# OLD_Main.net
KiCad netlist of a schematic drawn in Altium Designer
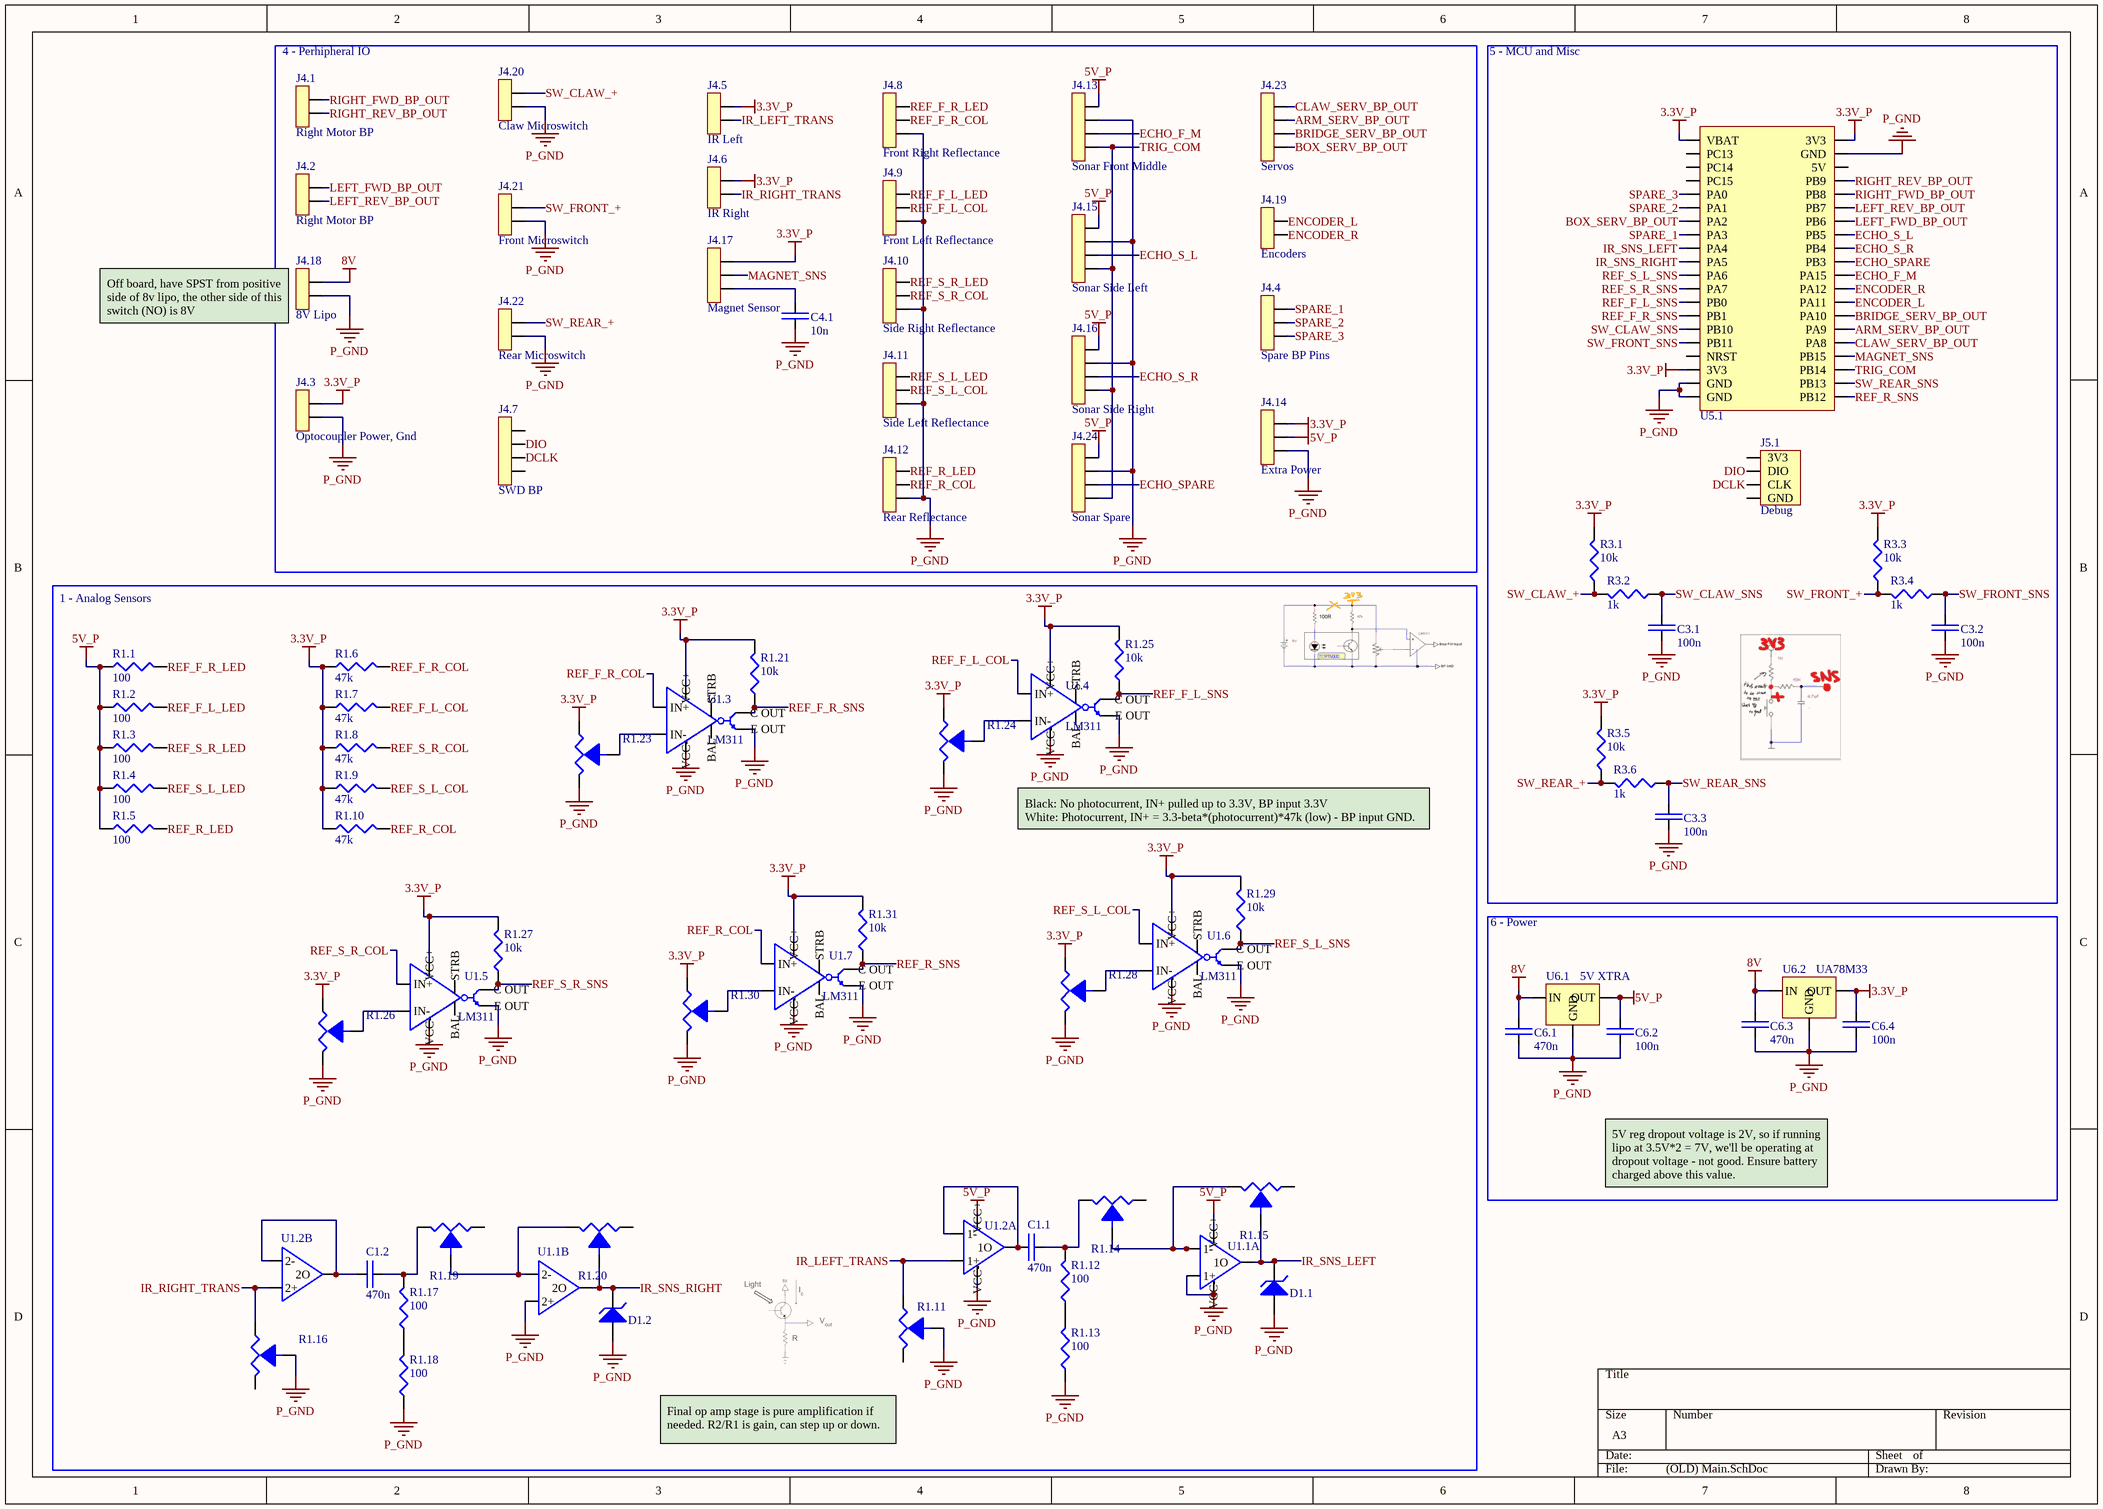
[diagram p0: (OLD) Main.SchDoc]

(export (version "E")
  (design (tool "Eeschema 10.0.6"))
  (components
    (comp (ref "C1.1")
      (value "470n")
      (footprint "Non Polarized Cap")
      (libsource (lib "SPICEBot_SchLib") (part "Cap_Generic"))
    )
    (comp (ref "C1.2")
      (value "470n")
      (footprint "Non Polarized Cap")
      (libsource (lib "SPICEBot_SchLib") (part "Cap_Generic"))
    )
    (comp (ref "C3.1")
      (value "100n")
      (footprint "Non Polarized Cap")
      (libsource (lib "SPICEBot_SchLib") (part "Cap_Generic"))
    )
    (comp (ref "C3.2")
      (value "100n")
      (footprint "Non Polarized Cap")
      (libsource (lib "SPICEBot_SchLib") (part "Cap_Generic"))
    )
    (comp (ref "C3.3")
      (value "100n")
      (footprint "Non Polarized Cap")
      (libsource (lib "SPICEBot_SchLib") (part "Cap_Generic"))
    )
    (comp (ref "C4.1")
      (value "10n")
      (footprint "Non Polarized Cap")
      (libsource (lib "SPICEBot_SchLib") (part "Cap_Generic"))
    )
    (comp (ref "C6.1")
      (value "470n")
      (footprint "Non Polarized Cap")
      (libsource (lib "SPICEBot_SchLib") (part "Cap_Generic"))
    )
    (comp (ref "C6.2")
      (value "100n")
      (footprint "Non Polarized Cap")
      (libsource (lib "SPICEBot_SchLib") (part "Cap_Generic"))
    )
    (comp (ref "C6.3")
      (value "470n")
      (footprint "Non Polarized Cap")
      (libsource (lib "SPICEBot_SchLib") (part "Cap_Generic"))
    )
    (comp (ref "C6.4")
      (value "100n")
      (footprint "Non Polarized Cap")
      (libsource (lib "SPICEBot_SchLib") (part "Cap_Generic"))
    )
    (comp (ref "D1.1")
      (value "3.3V")
      (footprint "Zener Generic")
      (libsource (lib "SPICEBot_SchLib") (part "Zener_Generic"))
    )
    (comp (ref "D1.2")
      (value "3.3V")
      (footprint "Zener Generic")
      (libsource (lib "SPICEBot_SchLib") (part "Zener_Generic"))
    )
    (comp (ref "J4.1")
      (value "Right Motor BP")
      (footprint "2pos JST")
      (description "2pos Conn JST")
      (libsource (lib "SPICEBot_SchLib") (part "2pos Conn"))
    )
    (comp (ref "J4.2")
      (value "Right Motor BP")
      (footprint "2pos JST")
      (description "2pos Conn JST")
      (libsource (lib "SPICEBot_SchLib") (part "2pos Conn"))
    )
    (comp (ref "J4.3")
      (value "Optocoupler Power, Gnd")
      (footprint "2pos JST")
      (description "2pos Conn JST")
      (libsource (lib "SPICEBot_SchLib") (part "2pos Conn"))
    )
    (comp (ref "J4.4")
      (value "Spare BP Pins")
      (footprint "3pos JST")
      (description "3pos Conn")
      (libsource (lib "SPICEBot_SchLib") (part "3pos Conn"))
    )
    (comp (ref "J4.5")
      (value "IR Left")
      (footprint "2pos JST")
      (description "2pos Conn JST")
      (libsource (lib "SPICEBot_SchLib") (part "2pos Conn"))
    )
    (comp (ref "J4.6")
      (value "IR Right")
      (footprint "2pos JST")
      (description "2pos Conn JST")
      (libsource (lib "SPICEBot_SchLib") (part "2pos Conn"))
    )
    (comp (ref "J4.7")
      (value "SWD BP")
      (footprint "4Pos JST")
      (description "4pos Conn")
      (libsource (lib "SPICEBot_SchLib") (part "4pos Conn"))
    )
    (comp (ref "J4.8")
      (value "Front Right Reflectance")
      (footprint "3pos JST")
      (description "3pos Conn")
      (libsource (lib "SPICEBot_SchLib") (part "3pos Conn"))
    )
    (comp (ref "J4.9")
      (value "Front Left Reflectance")
      (footprint "3pos JST")
      (description "3pos Conn")
      (libsource (lib "SPICEBot_SchLib") (part "3pos Conn"))
    )
    (comp (ref "J4.10")
      (value "Side Right Reflectance")
      (footprint "3pos JST")
      (description "3pos Conn")
      (libsource (lib "SPICEBot_SchLib") (part "3pos Conn"))
    )
    (comp (ref "J4.11")
      (value "Side Left Reflectance")
      (footprint "3pos JST")
      (description "3pos Conn")
      (libsource (lib "SPICEBot_SchLib") (part "3pos Conn"))
    )
    (comp (ref "J4.12")
      (value "Rear Reflectance")
      (footprint "3pos JST")
      (description "3pos Conn")
      (libsource (lib "SPICEBot_SchLib") (part "3pos Conn"))
    )
    (comp (ref "J4.13")
      (value "Sonar Front Middle")
      (footprint "4Pos JST")
      (description "4pos Conn")
      (libsource (lib "SPICEBot_SchLib") (part "4pos Conn"))
    )
    (comp (ref "J4.14")
      (value "Extra Power")
      (footprint "3pos JST")
      (description "3pos Conn")
      (libsource (lib "SPICEBot_SchLib") (part "3pos Conn"))
    )
    (comp (ref "J4.15")
      (value "Sonar Side Left")
      (footprint "4Pos JST")
      (description "4pos Conn")
      (libsource (lib "SPICEBot_SchLib") (part "4pos Conn"))
    )
    (comp (ref "J4.16")
      (value "Sonar Side Right")
      (footprint "4Pos JST")
      (description "4pos Conn")
      (libsource (lib "SPICEBot_SchLib") (part "4pos Conn"))
    )
    (comp (ref "J4.17")
      (value "Magnet Sensor")
      (footprint "3pos JST")
      (description "3pos Conn")
      (libsource (lib "SPICEBot_SchLib") (part "3pos Conn"))
    )
    (comp (ref "J4.18")
      (value "8V Lipo")
      (footprint "2pos JST")
      (description "2pos Conn JST")
      (libsource (lib "SPICEBot_SchLib") (part "2pos Conn"))
    )
    (comp (ref "J4.19")
      (value "Encoders")
      (footprint "2pos JST")
      (description "2pos Conn JST")
      (libsource (lib "SPICEBot_SchLib") (part "2pos Conn"))
    )
    (comp (ref "J4.20")
      (value "Claw Microswitch")
      (footprint "2pos JST")
      (description "2pos Conn JST")
      (libsource (lib "SPICEBot_SchLib") (part "2pos Conn"))
    )
    (comp (ref "J4.21")
      (value "Front Microswitch")
      (footprint "2pos JST")
      (description "2pos Conn JST")
      (libsource (lib "SPICEBot_SchLib") (part "2pos Conn"))
    )
    (comp (ref "J4.22")
      (value "Rear Microswitch")
      (footprint "2pos JST")
      (description "2pos Conn JST")
      (libsource (lib "SPICEBot_SchLib") (part "2pos Conn"))
    )
    (comp (ref "J4.23")
      (value "Servos")
      (footprint "4Pos JST")
      (description "4pos Conn")
      (libsource (lib "SPICEBot_SchLib") (part "4pos Conn"))
    )
    (comp (ref "J4.24")
      (value "Sonar Spare")
      (footprint "4Pos JST")
      (description "4pos Conn")
      (libsource (lib "SPICEBot_SchLib") (part "4pos Conn"))
    )
    (comp (ref "J5.1")
      (value "Debug")
      (footprint "Four Pads")
      (libsource (lib "SPICEBot_SchLib") (part "BP SWD Conn"))
    )
    (comp (ref "R1.1")
      (value "100")
      (footprint "Res_Generic")
      (libsource (lib "SPICEBot_SchLib") (part "Res_Generic"))
    )
    (comp (ref "R1.2")
      (value "100")
      (footprint "Res_Generic")
      (libsource (lib "SPICEBot_SchLib") (part "Res_Generic"))
    )
    (comp (ref "R1.3")
      (value "100")
      (footprint "Res_Generic")
      (libsource (lib "SPICEBot_SchLib") (part "Res_Generic"))
    )
    (comp (ref "R1.4")
      (value "100")
      (footprint "Res_Generic")
      (libsource (lib "SPICEBot_SchLib") (part "Res_Generic"))
    )
    (comp (ref "R1.5")
      (value "100")
      (footprint "Res_Generic")
      (libsource (lib "SPICEBot_SchLib") (part "Res_Generic"))
    )
    (comp (ref "R1.6")
      (value "47k")
      (footprint "Res_Generic")
      (libsource (lib "SPICEBot_SchLib") (part "Res_Generic"))
    )
    (comp (ref "R1.7")
      (value "47k")
      (footprint "Res_Generic")
      (libsource (lib "SPICEBot_SchLib") (part "Res_Generic"))
    )
    (comp (ref "R1.8")
      (value "47k")
      (footprint "Res_Generic")
      (libsource (lib "SPICEBot_SchLib") (part "Res_Generic"))
    )
    (comp (ref "R1.9")
      (value "47k")
      (footprint "Res_Generic")
      (libsource (lib "SPICEBot_SchLib") (part "Res_Generic"))
    )
    (comp (ref "R1.10")
      (value "47k")
      (footprint "Res_Generic")
      (libsource (lib "SPICEBot_SchLib") (part "Res_Generic"))
    )
    (comp (ref "R1.11")
      (value "100k")
      (footprint "Pot Generic")
      (libsource (lib "SPICEBot_SchLib") (part "Pot_Generic"))
    )
    (comp (ref "R1.12")
      (value "100")
      (footprint "Res_Generic")
      (libsource (lib "SPICEBot_SchLib") (part "Res_Generic"))
    )
    (comp (ref "R1.13")
      (value "100")
      (footprint "Res_Generic")
      (libsource (lib "SPICEBot_SchLib") (part "Res_Generic"))
    )
    (comp (ref "R1.14")
      (value "10k")
      (footprint "Pot Generic")
      (libsource (lib "SPICEBot_SchLib") (part "Pot_Generic"))
    )
    (comp (ref "R1.15")
      (value "100k")
      (footprint "Pot Generic")
      (libsource (lib "SPICEBot_SchLib") (part "Pot_Generic"))
    )
    (comp (ref "R1.16")
      (value "100k")
      (footprint "Pot Generic")
      (libsource (lib "SPICEBot_SchLib") (part "Pot_Generic"))
    )
    (comp (ref "R1.17")
      (value "100")
      (footprint "Res_Generic")
      (libsource (lib "SPICEBot_SchLib") (part "Res_Generic"))
    )
    (comp (ref "R1.18")
      (value "100")
      (footprint "Res_Generic")
      (libsource (lib "SPICEBot_SchLib") (part "Res_Generic"))
    )
    (comp (ref "R1.19")
      (value "10k")
      (footprint "Pot Generic")
      (libsource (lib "SPICEBot_SchLib") (part "Pot_Generic"))
    )
    (comp (ref "R1.20")
      (value "100k")
      (footprint "Pot Generic")
      (libsource (lib "SPICEBot_SchLib") (part "Pot_Generic"))
    )
    (comp (ref "R1.21")
      (value "10k")
      (footprint "Res_Generic")
      (libsource (lib "SPICEBot_SchLib") (part "Res_Generic"))
    )
    (comp (ref "R1.23")
      (value "10k")
      (footprint "Pot Generic")
      (libsource (lib "SPICEBot_SchLib") (part "Pot_Generic"))
    )
    (comp (ref "R1.24")
      (value "10k")
      (footprint "Pot Generic")
      (libsource (lib "SPICEBot_SchLib") (part "Pot_Generic"))
    )
    (comp (ref "R1.25")
      (value "10k")
      (footprint "Res_Generic")
      (libsource (lib "SPICEBot_SchLib") (part "Res_Generic"))
    )
    (comp (ref "R1.26")
      (value "10k")
      (footprint "Pot Generic")
      (libsource (lib "SPICEBot_SchLib") (part "Pot_Generic"))
    )
    (comp (ref "R1.27")
      (value "10k")
      (footprint "Res_Generic")
      (libsource (lib "SPICEBot_SchLib") (part "Res_Generic"))
    )
    (comp (ref "R1.28")
      (value "10k")
      (footprint "Pot Generic")
      (libsource (lib "SPICEBot_SchLib") (part "Pot_Generic"))
    )
    (comp (ref "R1.29")
      (value "10k")
      (footprint "Res_Generic")
      (libsource (lib "SPICEBot_SchLib") (part "Res_Generic"))
    )
    (comp (ref "R1.30")
      (value "10k")
      (footprint "Pot Generic")
      (libsource (lib "SPICEBot_SchLib") (part "Pot_Generic"))
    )
    (comp (ref "R1.31")
      (value "10k")
      (footprint "Res_Generic")
      (libsource (lib "SPICEBot_SchLib") (part "Res_Generic"))
    )
    (comp (ref "R3.1")
      (value "10k")
      (footprint "Res_Generic")
      (libsource (lib "SPICEBot_SchLib") (part "Res_Generic"))
    )
    (comp (ref "R3.2")
      (value "1k")
      (footprint "Res_Generic")
      (libsource (lib "SPICEBot_SchLib") (part "Res_Generic"))
    )
    (comp (ref "R3.3")
      (value "10k")
      (footprint "Res_Generic")
      (libsource (lib "SPICEBot_SchLib") (part "Res_Generic"))
    )
    (comp (ref "R3.4")
      (value "1k")
      (footprint "Res_Generic")
      (libsource (lib "SPICEBot_SchLib") (part "Res_Generic"))
    )
    (comp (ref "R3.5")
      (value "10k")
      (footprint "Res_Generic")
      (libsource (lib "SPICEBot_SchLib") (part "Res_Generic"))
    )
    (comp (ref "R3.6")
      (value "1k")
      (footprint "Res_Generic")
      (libsource (lib "SPICEBot_SchLib") (part "Res_Generic"))
    )
    (comp (ref "U1.1")
      (value "TL082IP")
      (footprint "DIP8")
      (description "TL082IP IC OPAMP JFET 2 CIRCUIT 8DIP")
      (libsource (lib "SPICEBot_SchLib") (part "TL082IP Op Amp"))
    )
    (comp (ref "U1.2")
      (value "TL082IP")
      (footprint "DIP8")
      (description "TL082IP IC OPAMP JFET 2 CIRCUIT 8DIP")
      (libsource (lib "SPICEBot_SchLib") (part "TL082IP Op Amp"))
    )
    (comp (ref "U1.3")
      (value "LM311")
      (footprint "DIP8")
      (description "LM311 IC DIFF COMPARATOR STROBE 8-DIP")
      (libsource (lib "SPICEBot_SchLib") (part "LM311 Comparator"))
    )
    (comp (ref "U1.4")
      (value "LM311")
      (footprint "DIP8")
      (description "LM311 IC DIFF COMPARATOR STROBE 8-DIP")
      (libsource (lib "SPICEBot_SchLib") (part "LM311 Comparator"))
    )
    (comp (ref "U1.5")
      (value "LM311")
      (footprint "DIP8")
      (description "LM311 IC DIFF COMPARATOR STROBE 8-DIP")
      (libsource (lib "SPICEBot_SchLib") (part "LM311 Comparator"))
    )
    (comp (ref "U1.6")
      (value "LM311")
      (footprint "DIP8")
      (description "LM311 IC DIFF COMPARATOR STROBE 8-DIP")
      (libsource (lib "SPICEBot_SchLib") (part "LM311 Comparator"))
    )
    (comp (ref "U1.7")
      (value "LM311")
      (footprint "DIP8")
      (description "LM311 IC DIFF COMPARATOR STROBE 8-DIP")
      (libsource (lib "SPICEBot_SchLib") (part "LM311 Comparator"))
    )
    (comp (ref "U5.1")
      (value "Bluepill")
      (footprint "DIP40")
      (description "STM32F103C8T6")
      (libsource (lib "SPICEBot_SchLib") (part "Bluepill"))
    )
    (comp (ref "U6.1")
      (value "5V XTRA")
      (footprint "TO220")
      (description "UA7805 IC REG LINEAR 5V 1.5A TO220-3")
      (libsource (lib "SPICEBot_SchLib") (part "UA7805 5V Reg"))
    )
    (comp (ref "U6.2")
      (value "UA78M33")
      (footprint "TO220")
      (description "UA78M33 IC REG LINEAR 3.3V 500MA TO220-3")
      (libsource (lib "SPICEBot_SchLib") (part "UA78M33CKCS 3.3V Reg"))
    )
  )
  (nets
    (net (code "1") (name "/ARM_SERV_BP_OUT") (class "Default")
      (node (ref "J4.23") (pin "3") (pinfunction "3_3") (pintype "passive"))
      (node (ref "U5.1") (pin "26") (pinfunction "PA9_26") (pintype "passive"))
    )
    (net (code "2") (name "/BOX_SERV_BP_OUT") (class "Default")
      (node (ref "J4.23") (pin "1") (pinfunction "1_1") (pintype "passive"))
      (node (ref "U5.1") (pin "7") (pinfunction "PA2_7") (pintype "passive"))
    )
    (net (code "3") (name "/BRIDGE_SERV_BP_OUT") (class "Default")
      (node (ref "J4.23") (pin "2") (pinfunction "2_2") (pintype "passive"))
      (node (ref "U5.1") (pin "27") (pinfunction "PA10_27") (pintype "passive"))
    )
    (net (code "4") (name "/CLAW_SERV_BP_OUT") (class "Default")
      (node (ref "J4.23") (pin "4") (pinfunction "4_4") (pintype "passive"))
      (node (ref "U5.1") (pin "25") (pinfunction "PA8_25") (pintype "passive"))
    )
    (net (code "5") (name "/DCLK") (class "Default")
      (node (ref "J4.7") (pin "2") (pinfunction "2_2") (pintype "passive"))
      (node (ref "J5.1") (pin "3") (pinfunction "CLK_3") (pintype "passive"))
    )
    (net (code "6") (name "/DIO") (class "Default")
      (node (ref "J4.7") (pin "3") (pinfunction "3_3") (pintype "passive"))
      (node (ref "J5.1") (pin "2") (pinfunction "DIO_2") (pintype "passive"))
    )
    (net (code "7") (name "/ECHO_F_M") (class "Default")
      (node (ref "J4.13") (pin "2") (pinfunction "2_2") (pintype "passive"))
      (node (ref "U5.1") (pin "30") (pinfunction "PA15_30") (pintype "passive"))
    )
    (net (code "8") (name "/ECHO_SPARE") (class "Default")
      (node (ref "J4.24") (pin "2") (pinfunction "2_2") (pintype "passive"))
      (node (ref "U5.1") (pin "31") (pinfunction "PB3_31") (pintype "passive"))
    )
    (net (code "9") (name "/ECHO_S_L") (class "Default")
      (node (ref "J4.15") (pin "2") (pinfunction "2_2") (pintype "passive"))
      (node (ref "U5.1") (pin "33") (pinfunction "PB5_33") (pintype "passive"))
    )
    (net (code "10") (name "/ECHO_S_R") (class "Default")
      (node (ref "J4.16") (pin "2") (pinfunction "2_2") (pintype "passive"))
      (node (ref "U5.1") (pin "32") (pinfunction "PB4_32") (pintype "passive"))
    )
    (net (code "11") (name "/ENCODER_L") (class "Default")
      (node (ref "J4.19") (pin "2") (pinfunction "2_2") (pintype "passive"))
      (node (ref "U5.1") (pin "28") (pinfunction "PA11_28") (pintype "passive"))
    )
    (net (code "12") (name "/ENCODER_R") (class "Default")
      (node (ref "J4.19") (pin "1") (pinfunction "1_1") (pintype "passive"))
      (node (ref "U5.1") (pin "29") (pinfunction "PA12_29") (pintype "passive"))
    )
    (net (code "13") (name "/IR_LEFT_TRANS") (class "Default")
      (node (ref "J4.5") (pin "1") (pinfunction "1_1") (pintype "passive"))
      (node (ref "R1.11") (pin "3") (pinfunction "3_3") (pintype "passive"))
      (node (ref "U1.2") (pin "3") (pinfunction "1+_3") (pintype "passive"))
    )
    (net (code "14") (name "/IR_RIGHT_TRANS") (class "Default")
      (node (ref "J4.6") (pin "1") (pinfunction "1_1") (pintype "passive"))
      (node (ref "R1.16") (pin "3") (pinfunction "3_3") (pintype "passive"))
      (node (ref "U1.2") (pin "5") (pinfunction "2+_5") (pintype "passive"))
    )
    (net (code "15") (name "/IR_SNS_LEFT") (class "Default")
      (node (ref "D1.1") (pin "2") (pinfunction "Cathode_2") (pintype "passive"))
      (node (ref "R1.15") (pin "2") (pinfunction "2_2") (pintype "passive"))
      (node (ref "U1.1") (pin "1") (pinfunction "1O_1") (pintype "passive"))
      (node (ref "U5.1") (pin "9") (pinfunction "PA4_9") (pintype "passive"))
    )
    (net (code "16") (name "/IR_SNS_RIGHT") (class "Default")
      (node (ref "D1.2") (pin "2") (pinfunction "Cathode_2") (pintype "passive"))
      (node (ref "R1.20") (pin "2") (pinfunction "2_2") (pintype "passive"))
      (node (ref "U1.1") (pin "7") (pinfunction "2O_7") (pintype "passive"))
      (node (ref "U5.1") (pin "10") (pinfunction "PA5_10") (pintype "passive"))
    )
    (net (code "17") (name "/LEFT_FWD_BP_OUT") (class "Default")
      (node (ref "J4.2") (pin "2") (pinfunction "2_2") (pintype "passive"))
      (node (ref "U5.1") (pin "34") (pinfunction "PB6_34") (pintype "passive"))
    )
    (net (code "18") (name "/LEFT_REV_BP_OUT") (class "Default")
      (node (ref "J4.2") (pin "1") (pinfunction "1_1") (pintype "passive"))
      (node (ref "U5.1") (pin "35") (pinfunction "PB7_35") (pintype "passive"))
    )
    (net (code "19") (name "/MAGNET_SNS") (class "Default")
      (node (ref "J4.17") (pin "2") (pinfunction "2_2") (pintype "passive"))
      (node (ref "U5.1") (pin "24") (pinfunction "PB15_24") (pintype "passive"))
    )
    (net (code "20") (name "/REF_F_L_COL") (class "Default")
      (node (ref "J4.9") (pin "2") (pinfunction "2_2") (pintype "passive"))
      (node (ref "R1.7") (pin "2") (pinfunction "2_2") (pintype "passive"))
      (node (ref "U1.4") (pin "2") (pinfunction "IN+_2") (pintype "passive"))
    )
    (net (code "21") (name "/REF_F_L_LED") (class "Default")
      (node (ref "J4.9") (pin "3") (pinfunction "3_3") (pintype "passive"))
      (node (ref "R1.2") (pin "2") (pinfunction "2_2") (pintype "passive"))
    )
    (net (code "22") (name "/REF_F_L_SNS") (class "Default")
      (node (ref "R1.25") (pin "1") (pinfunction "1_1") (pintype "passive"))
      (node (ref "U1.4") (pin "7") (pinfunction "C_OUT_7") (pintype "passive"))
      (node (ref "U5.1") (pin "13") (pinfunction "PB0_13") (pintype "passive"))
    )
    (net (code "23") (name "/REF_F_R_COL") (class "Default")
      (node (ref "J4.8") (pin "2") (pinfunction "2_2") (pintype "passive"))
      (node (ref "R1.6") (pin "2") (pinfunction "2_2") (pintype "passive"))
      (node (ref "U1.3") (pin "2") (pinfunction "IN+_2") (pintype "passive"))
    )
    (net (code "24") (name "/REF_F_R_LED") (class "Default")
      (node (ref "J4.8") (pin "3") (pinfunction "3_3") (pintype "passive"))
      (node (ref "R1.1") (pin "2") (pinfunction "2_2") (pintype "passive"))
    )
    (net (code "25") (name "/REF_F_R_SNS") (class "Default")
      (node (ref "R1.21") (pin "1") (pinfunction "1_1") (pintype "passive"))
      (node (ref "U1.3") (pin "7") (pinfunction "C_OUT_7") (pintype "passive"))
      (node (ref "U5.1") (pin "14") (pinfunction "PB1_14") (pintype "passive"))
    )
    (net (code "26") (name "/REF_R_COL") (class "Default")
      (node (ref "J4.12") (pin "2") (pinfunction "2_2") (pintype "passive"))
      (node (ref "R1.10") (pin "2") (pinfunction "2_2") (pintype "passive"))
      (node (ref "U1.7") (pin "2") (pinfunction "IN+_2") (pintype "passive"))
    )
    (net (code "27") (name "/REF_R_LED") (class "Default")
      (node (ref "J4.12") (pin "3") (pinfunction "3_3") (pintype "passive"))
      (node (ref "R1.5") (pin "2") (pinfunction "2_2") (pintype "passive"))
    )
    (net (code "28") (name "/REF_R_SNS") (class "Default")
      (node (ref "R1.31") (pin "1") (pinfunction "1_1") (pintype "passive"))
      (node (ref "U1.7") (pin "7") (pinfunction "C_OUT_7") (pintype "passive"))
      (node (ref "U5.1") (pin "21") (pinfunction "PB12_21") (pintype "passive"))
    )
    (net (code "29") (name "/REF_S_L_COL") (class "Default")
      (node (ref "J4.11") (pin "2") (pinfunction "2_2") (pintype "passive"))
      (node (ref "R1.9") (pin "2") (pinfunction "2_2") (pintype "passive"))
      (node (ref "U1.6") (pin "2") (pinfunction "IN+_2") (pintype "passive"))
    )
    (net (code "30") (name "/REF_S_L_LED") (class "Default")
      (node (ref "J4.11") (pin "3") (pinfunction "3_3") (pintype "passive"))
      (node (ref "R1.4") (pin "2") (pinfunction "2_2") (pintype "passive"))
    )
    (net (code "31") (name "/REF_S_L_SNS") (class "Default")
      (node (ref "R1.29") (pin "1") (pinfunction "1_1") (pintype "passive"))
      (node (ref "U1.6") (pin "7") (pinfunction "C_OUT_7") (pintype "passive"))
      (node (ref "U5.1") (pin "11") (pinfunction "PA6_11") (pintype "passive"))
    )
    (net (code "32") (name "/REF_S_R_COL") (class "Default")
      (node (ref "J4.10") (pin "2") (pinfunction "2_2") (pintype "passive"))
      (node (ref "R1.8") (pin "2") (pinfunction "2_2") (pintype "passive"))
      (node (ref "U1.5") (pin "2") (pinfunction "IN+_2") (pintype "passive"))
    )
    (net (code "33") (name "/REF_S_R_LED") (class "Default")
      (node (ref "J4.10") (pin "3") (pinfunction "3_3") (pintype "passive"))
      (node (ref "R1.3") (pin "2") (pinfunction "2_2") (pintype "passive"))
    )
    (net (code "34") (name "/REF_S_R_SNS") (class "Default")
      (node (ref "R1.27") (pin "1") (pinfunction "1_1") (pintype "passive"))
      (node (ref "U1.5") (pin "7") (pinfunction "C_OUT_7") (pintype "passive"))
      (node (ref "U5.1") (pin "12") (pinfunction "PA7_12") (pintype "passive"))
    )
    (net (code "35") (name "/RIGHT_FWD_BP_OUT") (class "Default")
      (node (ref "J4.1") (pin "2") (pinfunction "2_2") (pintype "passive"))
      (node (ref "U5.1") (pin "36") (pinfunction "PB8_36") (pintype "passive"))
    )
    (net (code "36") (name "/RIGHT_REV_BP_OUT") (class "Default")
      (node (ref "J4.1") (pin "1") (pinfunction "1_1") (pintype "passive"))
      (node (ref "U5.1") (pin "37") (pinfunction "PB9_37") (pintype "passive"))
    )
    (net (code "37") (name "/SPARE_1") (class "Default")
      (node (ref "J4.4") (pin "3") (pinfunction "3_3") (pintype "passive"))
      (node (ref "U5.1") (pin "8") (pinfunction "PA3_8") (pintype "passive"))
    )
    (net (code "38") (name "/SPARE_2") (class "Default")
      (node (ref "J4.4") (pin "2") (pinfunction "2_2") (pintype "passive"))
      (node (ref "U5.1") (pin "6") (pinfunction "PA1_6") (pintype "passive"))
    )
    (net (code "39") (name "/SPARE_3") (class "Default")
      (node (ref "J4.4") (pin "1") (pinfunction "1_1") (pintype "passive"))
      (node (ref "U5.1") (pin "5") (pinfunction "PA0_5") (pintype "passive"))
    )
    (net (code "40") (name "/SW_CLAW_+") (class "Default")
      (node (ref "J4.20") (pin "2") (pinfunction "2_2") (pintype "passive"))
      (node (ref "R3.1") (pin "1") (pinfunction "1_1") (pintype "passive"))
      (node (ref "R3.2") (pin "2") (pinfunction "2_2") (pintype "passive"))
    )
    (net (code "41") (name "/SW_CLAW_SNS") (class "Default")
      (node (ref "C3.1") (pin "2") (pinfunction "2_2") (pintype "passive"))
      (node (ref "R3.2") (pin "1") (pinfunction "1_1") (pintype "passive"))
      (node (ref "U5.1") (pin "15") (pinfunction "PB10_15") (pintype "passive"))
    )
    (net (code "42") (name "/SW_FRONT_+") (class "Default")
      (node (ref "J4.21") (pin "2") (pinfunction "2_2") (pintype "passive"))
      (node (ref "R3.3") (pin "1") (pinfunction "1_1") (pintype "passive"))
      (node (ref "R3.4") (pin "2") (pinfunction "2_2") (pintype "passive"))
    )
    (net (code "43") (name "/SW_FRONT_SNS") (class "Default")
      (node (ref "C3.2") (pin "2") (pinfunction "2_2") (pintype "passive"))
      (node (ref "R3.4") (pin "1") (pinfunction "1_1") (pintype "passive"))
      (node (ref "U5.1") (pin "16") (pinfunction "PB11_16") (pintype "passive"))
    )
    (net (code "44") (name "/SW_REAR_+") (class "Default")
      (node (ref "J4.22") (pin "2") (pinfunction "2_2") (pintype "passive"))
      (node (ref "R3.5") (pin "1") (pinfunction "1_1") (pintype "passive"))
      (node (ref "R3.6") (pin "2") (pinfunction "2_2") (pintype "passive"))
    )
    (net (code "45") (name "/SW_REAR_SNS") (class "Default")
      (node (ref "C3.3") (pin "2") (pinfunction "2_2") (pintype "passive"))
      (node (ref "R3.6") (pin "1") (pinfunction "1_1") (pintype "passive"))
      (node (ref "U5.1") (pin "22") (pinfunction "PB13_22") (pintype "passive"))
    )
    (net (code "46") (name "/TRIG_COM") (class "Default")
      (node (ref "J4.13") (pin "1") (pinfunction "1_1") (pintype "passive"))
      (node (ref "J4.15") (pin "1") (pinfunction "1_1") (pintype "passive"))
      (node (ref "J4.16") (pin "1") (pinfunction "1_1") (pintype "passive"))
      (node (ref "J4.24") (pin "1") (pinfunction "1_1") (pintype "passive"))
      (node (ref "U5.1") (pin "23") (pinfunction "PB14_23") (pintype "passive"))
    )
    (net (code "47") (name "3.3V_P") (class "Default")
      (node (ref "C6.4") (pin "2") (pinfunction "2_2") (pintype "passive"))
      (node (ref "J4.14") (pin "3") (pinfunction "3_3") (pintype "passive"))
      (node (ref "J4.17") (pin "3") (pinfunction "3_3") (pintype "passive"))
      (node (ref "J4.3") (pin "2") (pinfunction "2_2") (pintype "passive"))
      (node (ref "J4.5") (pin "2") (pinfunction "2_2") (pintype "passive"))
      (node (ref "J4.6") (pin "2") (pinfunction "2_2") (pintype "passive"))
      (node (ref "R1.10") (pin "1") (pinfunction "1_1") (pintype "passive"))
      (node (ref "R1.21") (pin "2") (pinfunction "2_2") (pintype "passive"))
      (node (ref "R1.23") (pin "3") (pinfunction "3_3") (pintype "passive"))
      (node (ref "R1.24") (pin "3") (pinfunction "3_3") (pintype "passive"))
      (node (ref "R1.25") (pin "2") (pinfunction "2_2") (pintype "passive"))
      (node (ref "R1.26") (pin "3") (pinfunction "3_3") (pintype "passive"))
      (node (ref "R1.27") (pin "2") (pinfunction "2_2") (pintype "passive"))
      (node (ref "R1.28") (pin "3") (pinfunction "3_3") (pintype "passive"))
      (node (ref "R1.29") (pin "2") (pinfunction "2_2") (pintype "passive"))
      (node (ref "R1.30") (pin "3") (pinfunction "3_3") (pintype "passive"))
      (node (ref "R1.31") (pin "2") (pinfunction "2_2") (pintype "passive"))
      (node (ref "R1.6") (pin "1") (pinfunction "1_1") (pintype "passive"))
      (node (ref "R1.7") (pin "1") (pinfunction "1_1") (pintype "passive"))
      (node (ref "R1.8") (pin "1") (pinfunction "1_1") (pintype "passive"))
      (node (ref "R1.9") (pin "1") (pinfunction "1_1") (pintype "passive"))
      (node (ref "R3.1") (pin "2") (pinfunction "2_2") (pintype "passive"))
      (node (ref "R3.3") (pin "2") (pinfunction "2_2") (pintype "passive"))
      (node (ref "R3.5") (pin "2") (pinfunction "2_2") (pintype "passive"))
      (node (ref "U1.3") (pin "8") (pinfunction "VCC+_8") (pintype "passive"))
      (node (ref "U1.4") (pin "8") (pinfunction "VCC+_8") (pintype "passive"))
      (node (ref "U1.5") (pin "8") (pinfunction "VCC+_8") (pintype "passive"))
      (node (ref "U1.6") (pin "8") (pinfunction "VCC+_8") (pintype "passive"))
      (node (ref "U1.7") (pin "8") (pinfunction "VCC+_8") (pintype "passive"))
      (node (ref "U5.1") (pin "1") (pinfunction "VBAT_1") (pintype "passive"))
      (node (ref "U5.1") (pin "18") (pinfunction "3V3_18") (pintype "passive"))
      (node (ref "U5.1") (pin "40") (pinfunction "3V3_40") (pintype "passive"))
      (node (ref "U6.2") (pin "3") (pinfunction "OUT_3") (pintype "passive"))
    )
    (net (code "48") (name "5V_P") (class "Default")
      (node (ref "C6.2") (pin "2") (pinfunction "2_2") (pintype "passive"))
      (node (ref "J4.13") (pin "4") (pinfunction "4_4") (pintype "passive"))
      (node (ref "J4.14") (pin "2") (pinfunction "2_2") (pintype "passive"))
      (node (ref "J4.15") (pin "4") (pinfunction "4_4") (pintype "passive"))
      (node (ref "J4.16") (pin "4") (pinfunction "4_4") (pintype "passive"))
      (node (ref "J4.24") (pin "4") (pinfunction "4_4") (pintype "passive"))
      (node (ref "R1.1") (pin "1") (pinfunction "1_1") (pintype "passive"))
      (node (ref "R1.2") (pin "1") (pinfunction "1_1") (pintype "passive"))
      (node (ref "R1.3") (pin "1") (pinfunction "1_1") (pintype "passive"))
      (node (ref "R1.4") (pin "1") (pinfunction "1_1") (pintype "passive"))
      (node (ref "R1.5") (pin "1") (pinfunction "1_1") (pintype "passive"))
      (node (ref "U1.1") (pin "8") (pinfunction "VCC+_8") (pintype "passive"))
      (node (ref "U1.2") (pin "8") (pinfunction "VCC+_8") (pintype "passive"))
      (node (ref "U6.1") (pin "3") (pinfunction "OUT_3") (pintype "passive"))
    )
    (net (code "49") (name "8V") (class "Default")
      (node (ref "C6.1") (pin "2") (pinfunction "2_2") (pintype "passive"))
      (node (ref "C6.3") (pin "2") (pinfunction "2_2") (pintype "passive"))
      (node (ref "J4.18") (pin "2") (pinfunction "2_2") (pintype "passive"))
      (node (ref "U6.1") (pin "1") (pinfunction "IN_1") (pintype "passive"))
      (node (ref "U6.2") (pin "1") (pinfunction "IN_1") (pintype "passive"))
    )
    (net (code "50") (name "Net-(C1.1-Pad2)") (class "Default")
      (node (ref "C1.1") (pin "2") (pinfunction "2_2") (pintype "passive"))
      (node (ref "R1.12") (pin "2") (pinfunction "2_2") (pintype "passive"))
      (node (ref "R1.14") (pin "1") (pinfunction "1_1") (pintype "passive"))
    )
    (net (code "51") (name "Net-(C1.2-Pad2)") (class "Default")
      (node (ref "C1.2") (pin "2") (pinfunction "2_2") (pintype "passive"))
      (node (ref "R1.17") (pin "2") (pinfunction "2_2") (pintype "passive"))
      (node (ref "R1.19") (pin "1") (pinfunction "1_1") (pintype "passive"))
    )
    (net (code "52") (name "Net-(C4.1-Pad2)") (class "Default")
      (node (ref "C4.1") (pin "2") (pinfunction "2_2") (pintype "passive"))
      (node (ref "J4.17") (pin "1") (pinfunction "1_1") (pintype "passive"))
    )
    (net (code "53") (name "Net-(R1.12-Pad1)") (class "Default")
      (node (ref "R1.12") (pin "1") (pinfunction "1_1") (pintype "passive"))
      (node (ref "R1.13") (pin "2") (pinfunction "2_2") (pintype "passive"))
    )
    (net (code "54") (name "Net-(R1.17-Pad1)") (class "Default")
      (node (ref "R1.17") (pin "1") (pinfunction "1_1") (pintype "passive"))
      (node (ref "R1.18") (pin "2") (pinfunction "2_2") (pintype "passive"))
    )
    (net (code "55") (name "Net-(U1.1A-1-)") (class "Default")
      (node (ref "R1.14") (pin "2") (pinfunction "2_2") (pintype "passive"))
      (node (ref "R1.15") (pin "1") (pinfunction "1_1") (pintype "passive"))
      (node (ref "U1.1") (pin "2") (pinfunction "1-_2") (pintype "passive"))
    )
    (net (code "56") (name "Net-(U1.1B-2-)") (class "Default")
      (node (ref "R1.19") (pin "2") (pinfunction "2_2") (pintype "passive"))
      (node (ref "R1.20") (pin "1") (pinfunction "1_1") (pintype "passive"))
      (node (ref "U1.1") (pin "6") (pinfunction "2-_6") (pintype "passive"))
    )
    (net (code "57") (name "Net-(U1.2A-1-)") (class "Default")
      (node (ref "C1.1") (pin "1") (pinfunction "1_1") (pintype "passive"))
      (node (ref "U1.2") (pin "1") (pinfunction "1O_1") (pintype "passive"))
      (node (ref "U1.2") (pin "2") (pinfunction "1-_2") (pintype "passive"))
    )
    (net (code "58") (name "Net-(U1.2B-2-)") (class "Default")
      (node (ref "C1.2") (pin "1") (pinfunction "1_1") (pintype "passive"))
      (node (ref "U1.2") (pin "6") (pinfunction "2-_6") (pintype "passive"))
      (node (ref "U1.2") (pin "7") (pinfunction "2O_7") (pintype "passive"))
    )
    (net (code "59") (name "Net-(U1.3-IN-)") (class "Default")
      (node (ref "R1.23") (pin "2") (pinfunction "2_2") (pintype "passive"))
      (node (ref "U1.3") (pin "3") (pinfunction "IN-_3") (pintype "passive"))
    )
    (net (code "60") (name "Net-(U1.4-IN-)") (class "Default")
      (node (ref "R1.24") (pin "2") (pinfunction "2_2") (pintype "passive"))
      (node (ref "U1.4") (pin "3") (pinfunction "IN-_3") (pintype "passive"))
    )
    (net (code "61") (name "Net-(U1.5-IN-)") (class "Default")
      (node (ref "R1.26") (pin "2") (pinfunction "2_2") (pintype "passive"))
      (node (ref "U1.5") (pin "3") (pinfunction "IN-_3") (pintype "passive"))
    )
    (net (code "62") (name "Net-(U1.6-IN-)") (class "Default")
      (node (ref "R1.28") (pin "2") (pinfunction "2_2") (pintype "passive"))
      (node (ref "U1.6") (pin "3") (pinfunction "IN-_3") (pintype "passive"))
    )
    (net (code "63") (name "Net-(U1.7-IN-)") (class "Default")
      (node (ref "R1.30") (pin "2") (pinfunction "2_2") (pintype "passive"))
      (node (ref "U1.7") (pin "3") (pinfunction "IN-_3") (pintype "passive"))
    )
    (net (code "64") (name "P_GND") (class "Default")
      (node (ref "C3.1") (pin "1") (pinfunction "1_1") (pintype "passive"))
      (node (ref "C3.2") (pin "1") (pinfunction "1_1") (pintype "passive"))
      (node (ref "C3.3") (pin "1") (pinfunction "1_1") (pintype "passive"))
      (node (ref "C4.1") (pin "1") (pinfunction "1_1") (pintype "passive"))
      (node (ref "C6.1") (pin "1") (pinfunction "1_1") (pintype "passive"))
      (node (ref "C6.2") (pin "1") (pinfunction "1_1") (pintype "passive"))
      (node (ref "C6.3") (pin "1") (pinfunction "1_1") (pintype "passive"))
      (node (ref "C6.4") (pin "1") (pinfunction "1_1") (pintype "passive"))
      (node (ref "D1.1") (pin "1") (pinfunction "Anode_1") (pintype "passive"))
      (node (ref "D1.2") (pin "1") (pinfunction "Anode_1") (pintype "passive"))
      (node (ref "J4.10") (pin "1") (pinfunction "1_1") (pintype "passive"))
      (node (ref "J4.11") (pin "1") (pinfunction "1_1") (pintype "passive"))
      (node (ref "J4.12") (pin "1") (pinfunction "1_1") (pintype "passive"))
      (node (ref "J4.13") (pin "3") (pinfunction "3_3") (pintype "passive"))
      (node (ref "J4.14") (pin "1") (pinfunction "1_1") (pintype "passive"))
      (node (ref "J4.15") (pin "3") (pinfunction "3_3") (pintype "passive"))
      (node (ref "J4.16") (pin "3") (pinfunction "3_3") (pintype "passive"))
      (node (ref "J4.18") (pin "1") (pinfunction "1_1") (pintype "passive"))
      (node (ref "J4.20") (pin "1") (pinfunction "1_1") (pintype "passive"))
      (node (ref "J4.21") (pin "1") (pinfunction "1_1") (pintype "passive"))
      (node (ref "J4.22") (pin "1") (pinfunction "1_1") (pintype "passive"))
      (node (ref "J4.24") (pin "3") (pinfunction "3_3") (pintype "passive"))
      (node (ref "J4.3") (pin "1") (pinfunction "1_1") (pintype "passive"))
      (node (ref "J4.8") (pin "1") (pinfunction "1_1") (pintype "passive"))
      (node (ref "J4.9") (pin "1") (pinfunction "1_1") (pintype "passive"))
      (node (ref "R1.11") (pin "2") (pinfunction "2_2") (pintype "passive"))
      (node (ref "R1.13") (pin "1") (pinfunction "1_1") (pintype "passive"))
      (node (ref "R1.16") (pin "2") (pinfunction "2_2") (pintype "passive"))
      (node (ref "R1.18") (pin "1") (pinfunction "1_1") (pintype "passive"))
      (node (ref "R1.23") (pin "1") (pinfunction "1_1") (pintype "passive"))
      (node (ref "R1.24") (pin "1") (pinfunction "1_1") (pintype "passive"))
      (node (ref "R1.26") (pin "1") (pinfunction "1_1") (pintype "passive"))
      (node (ref "R1.28") (pin "1") (pinfunction "1_1") (pintype "passive"))
      (node (ref "R1.30") (pin "1") (pinfunction "1_1") (pintype "passive"))
      (node (ref "U1.1") (pin "3") (pinfunction "1+_3") (pintype "passive"))
      (node (ref "U1.1") (pin "4") (pinfunction "VCC-_4") (pintype "passive"))
      (node (ref "U1.1") (pin "5") (pinfunction "2+_5") (pintype "passive"))
      (node (ref "U1.2") (pin "4") (pinfunction "VCC-_4") (pintype "passive"))
      (node (ref "U1.3") (pin "1") (pinfunction "E_OUT_1") (pintype "passive"))
      (node (ref "U1.3") (pin "4") (pinfunction "VCC-_4") (pintype "passive"))
      (node (ref "U1.4") (pin "1") (pinfunction "E_OUT_1") (pintype "passive"))
      (node (ref "U1.4") (pin "4") (pinfunction "VCC-_4") (pintype "passive"))
      (node (ref "U1.5") (pin "1") (pinfunction "E_OUT_1") (pintype "passive"))
      (node (ref "U1.5") (pin "4") (pinfunction "VCC-_4") (pintype "passive"))
      (node (ref "U1.6") (pin "1") (pinfunction "E_OUT_1") (pintype "passive"))
      (node (ref "U1.6") (pin "4") (pinfunction "VCC-_4") (pintype "passive"))
      (node (ref "U1.7") (pin "1") (pinfunction "E_OUT_1") (pintype "passive"))
      (node (ref "U1.7") (pin "4") (pinfunction "VCC-_4") (pintype "passive"))
      (node (ref "U5.1") (pin "19") (pinfunction "GND_19") (pintype "passive"))
      (node (ref "U5.1") (pin "20") (pinfunction "GND_20") (pintype "passive"))
      (node (ref "U5.1") (pin "39") (pinfunction "GND_39") (pintype "passive"))
      (node (ref "U6.1") (pin "2") (pinfunction "GND_2") (pintype "passive"))
      (node (ref "U6.2") (pin "2") (pinfunction "GND_2") (pintype "passive"))
    )
    (net (code "65") (name "unconnected-(J4.7-Pad1)") (class "Default")
      (node (ref "J4.7") (pin "1") (pinfunction "1_1") (pintype "passive"))
    )
    (net (code "66") (name "unconnected-(J4.7-Pad4)") (class "Default")
      (node (ref "J4.7") (pin "4") (pinfunction "4_4") (pintype "passive"))
    )
    (net (code "67") (name "unconnected-(J5.1-3V3-Pad1)") (class "Default")
      (node (ref "J5.1") (pin "1") (pinfunction "3V3_1") (pintype "passive"))
    )
    (net (code "68") (name "unconnected-(J5.1-GND-Pad4)") (class "Default")
      (node (ref "J5.1") (pin "4") (pinfunction "GND_4") (pintype "passive"))
    )
    (net (code "69") (name "unconnected-(R1.11-Pad1)") (class "Default")
      (node (ref "R1.11") (pin "1") (pinfunction "1_1") (pintype "passive"))
    )
    (net (code "70") (name "unconnected-(R1.14-Pad3)") (class "Default")
      (node (ref "R1.14") (pin "3") (pinfunction "3_3") (pintype "passive"))
    )
    (net (code "71") (name "unconnected-(R1.15-Pad3)") (class "Default")
      (node (ref "R1.15") (pin "3") (pinfunction "3_3") (pintype "passive"))
    )
    (net (code "72") (name "unconnected-(R1.16-Pad1)") (class "Default")
      (node (ref "R1.16") (pin "1") (pinfunction "1_1") (pintype "passive"))
    )
    (net (code "73") (name "unconnected-(R1.19-Pad3)") (class "Default")
      (node (ref "R1.19") (pin "3") (pinfunction "3_3") (pintype "passive"))
    )
    (net (code "74") (name "unconnected-(R1.20-Pad3)") (class "Default")
      (node (ref "R1.20") (pin "3") (pinfunction "3_3") (pintype "passive"))
    )
    (net (code "75") (name "unconnected-(U1.3-BAL-Pad5)") (class "Default")
      (node (ref "U1.3") (pin "5") (pinfunction "BAL_5") (pintype "passive"))
    )
    (net (code "76") (name "unconnected-(U1.3-STRB-Pad6)") (class "Default")
      (node (ref "U1.3") (pin "6") (pinfunction "STRB_6") (pintype "passive"))
    )
    (net (code "77") (name "unconnected-(U1.4-BAL-Pad5)") (class "Default")
      (node (ref "U1.4") (pin "5") (pinfunction "BAL_5") (pintype "passive"))
    )
    (net (code "78") (name "unconnected-(U1.4-STRB-Pad6)") (class "Default")
      (node (ref "U1.4") (pin "6") (pinfunction "STRB_6") (pintype "passive"))
    )
    (net (code "79") (name "unconnected-(U1.5-BAL-Pad5)") (class "Default")
      (node (ref "U1.5") (pin "5") (pinfunction "BAL_5") (pintype "passive"))
    )
    (net (code "80") (name "unconnected-(U1.5-STRB-Pad6)") (class "Default")
      (node (ref "U1.5") (pin "6") (pinfunction "STRB_6") (pintype "passive"))
    )
    (net (code "81") (name "unconnected-(U1.6-BAL-Pad5)") (class "Default")
      (node (ref "U1.6") (pin "5") (pinfunction "BAL_5") (pintype "passive"))
    )
    (net (code "82") (name "unconnected-(U1.6-STRB-Pad6)") (class "Default")
      (node (ref "U1.6") (pin "6") (pinfunction "STRB_6") (pintype "passive"))
    )
    (net (code "83") (name "unconnected-(U1.7-BAL-Pad5)") (class "Default")
      (node (ref "U1.7") (pin "5") (pinfunction "BAL_5") (pintype "passive"))
    )
    (net (code "84") (name "unconnected-(U1.7-STRB-Pad6)") (class "Default")
      (node (ref "U1.7") (pin "6") (pinfunction "STRB_6") (pintype "passive"))
    )
    (net (code "85") (name "unconnected-(U5.1-5V-Pad38)") (class "Default")
      (node (ref "U5.1") (pin "38") (pinfunction "5V_38") (pintype "passive"))
    )
    (net (code "86") (name "unconnected-(U5.1-NRST-Pad17)") (class "Default")
      (node (ref "U5.1") (pin "17") (pinfunction "NRST_17") (pintype "passive"))
    )
    (net (code "87") (name "unconnected-(U5.1-PC13-Pad2)") (class "Default")
      (node (ref "U5.1") (pin "2") (pinfunction "PC13_2") (pintype "passive"))
    )
    (net (code "88") (name "unconnected-(U5.1-PC14-Pad3)") (class "Default")
      (node (ref "U5.1") (pin "3") (pinfunction "PC14_3") (pintype "passive"))
    )
    (net (code "89") (name "unconnected-(U5.1-PC15-Pad4)") (class "Default")
      (node (ref "U5.1") (pin "4") (pinfunction "PC15_4") (pintype "passive"))
    )
  )
)
